# baterry.net
KiCad netlist of a schematic drawn in EAGLE
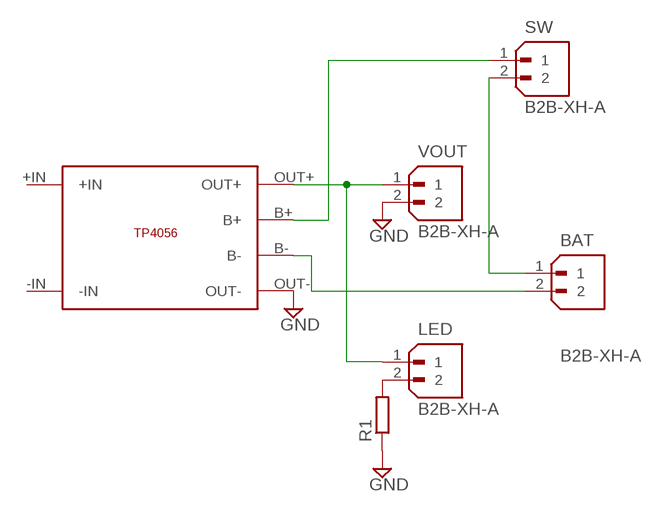
[diagram p0: schematic, sheet 1]

(export (version "E")
  (design (tool "Eeschema 10.0.6"))
  (components
    (comp (ref "BAT")
      (value "B2B-XH-A")
      (footprint "eagle-import:JST_B2B-XH-A")
      (fields (field (name "MF") "JST Sales"))
      (libsource (lib "eagle-import") (part "B2B-XH-A"))
    )
    (comp (ref "LED")
      (value "B2B-XH-A")
      (footprint "eagle-import:JST_B2B-XH-A")
      (fields (field (name "MF") "JST Sales"))
      (libsource (lib "eagle-import") (part "B2B-XH-A"))
    )
    (comp (ref "R1")
      (value "R-EU_0207/10")
      (footprint "eagle-import:0207_10")
      (libsource (lib "eagle-import") (part "R-EU_0207/10"))
    )
    (comp (ref "SW")
      (value "B2B-XH-A")
      (footprint "eagle-import:JST_B2B-XH-A")
      (fields (field (name "MF") "JST Sales"))
      (libsource (lib "eagle-import") (part "B2B-XH-A"))
    )
    (comp (ref "U$1")
      (value "TP4056")
      (footprint "eagle-import:TP4056")
      (libsource (lib "eagle-import") (part "TP4056"))
    )
    (comp (ref "VOUT")
      (value "B2B-XH-A")
      (footprint "eagle-import:JST_B2B-XH-A")
      (fields (field (name "MF") "JST Sales"))
      (libsource (lib "eagle-import") (part "B2B-XH-A"))
    )
  )
  (nets
    (net (code "1") (name "GND") (class "Default")
      (node (ref "R1") (pin "1") (pinfunction "1_1") (pintype "passive"))
      (node (ref "U$1") (pin "OUT-") (pinfunction "OUT-_OUT-") (pintype "bidirectional"))
      (node (ref "VOUT") (pin "2") (pinfunction "2_2") (pintype "passive"))
    )
    (net (code "2") (name "Net-(BAT-Pad1)") (class "Default")
      (node (ref "BAT") (pin "1") (pinfunction "1_1") (pintype "passive"))
      (node (ref "SW") (pin "2") (pinfunction "2_2") (pintype "passive"))
    )
    (net (code "3") (name "Net-(BAT-Pad2)") (class "Default")
      (node (ref "BAT") (pin "2") (pinfunction "2_2") (pintype "passive"))
      (node (ref "U$1") (pin "B-") (pinfunction "B-_B-") (pintype "bidirectional"))
    )
    (net (code "4") (name "Net-(LED-Pad1)") (class "Default")
      (node (ref "LED") (pin "1") (pinfunction "1_1") (pintype "passive"))
      (node (ref "U$1") (pin "OUT+") (pinfunction "OUT+_OUT+") (pintype "bidirectional"))
      (node (ref "VOUT") (pin "1") (pinfunction "1_1") (pintype "passive"))
    )
    (net (code "5") (name "Net-(LED-Pad2)") (class "Default")
      (node (ref "LED") (pin "2") (pinfunction "2_2") (pintype "passive"))
      (node (ref "R1") (pin "2") (pinfunction "2_2") (pintype "passive"))
    )
    (net (code "6") (name "Net-(SW-Pad1)") (class "Default")
      (node (ref "SW") (pin "1") (pinfunction "1_1") (pintype "passive"))
      (node (ref "U$1") (pin "B+") (pinfunction "B+_B+") (pintype "bidirectional"))
    )
    (net (code "7") (name "unconnected-(U$1-Pad+IN)") (class "Default")
      (node (ref "U$1") (pin "+IN") (pinfunction "+IN_+IN") (pintype "bidirectional"))
    )
    (net (code "8") (name "unconnected-(U$1-Pad-IN)") (class "Default")
      (node (ref "U$1") (pin "-IN") (pinfunction "-IN_-IN") (pintype "bidirectional"))
    )
  )
)
